# JTAG_Trace.net
KiCad netlist of a schematic drawn in Altium Designer
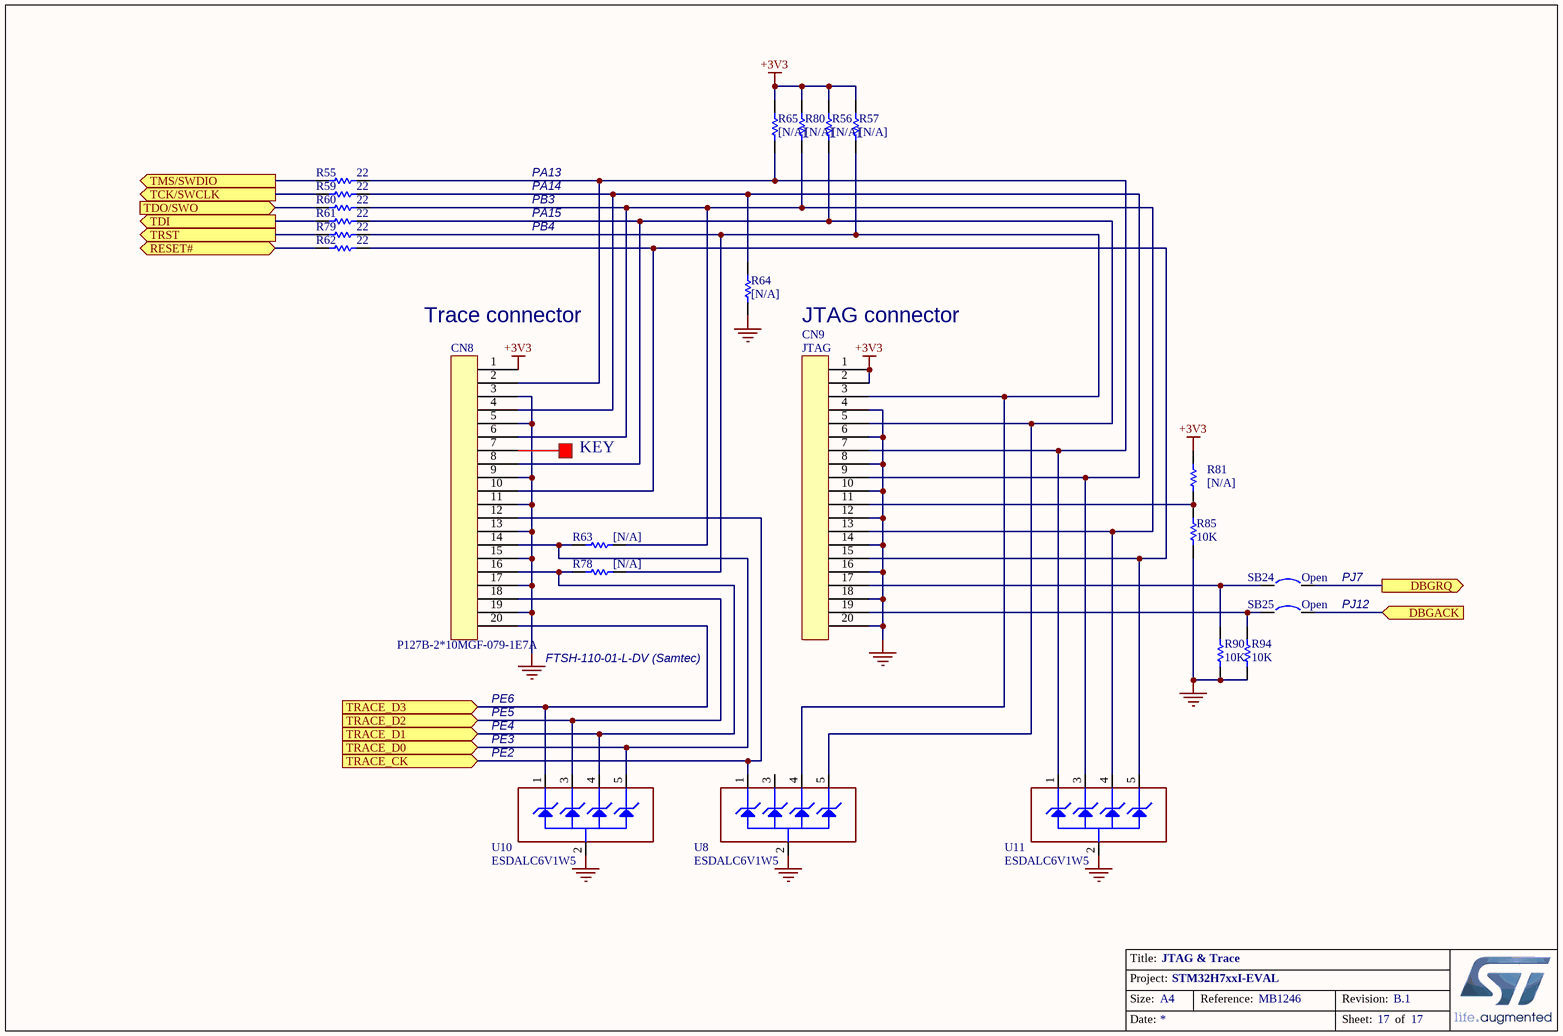
[diagram p0: JTAG&Trace.SchDoc]

(export (version "E")
  (design (tool "Eeschema 10.0.6"))
  (components
    (comp (ref "CN8")
      (value "P127B-2*10MGF-079-1E7A")
      (footprint "FTSH-110-01-L-DV")
      (libsource (lib "*") (part "20PIN1"))
    )
    (comp (ref "CN9") (value "JTAG") (footprint "IDC20S") (libsource (lib "*") (part "20PIN1")))
    (comp (ref "R55")
      (value "22")
      (footprint "0603R")
      (description "Resistor")
      (fields (field (name "PUBLISHER") "Altium Limited"))
      (libsource (lib "Miscellaneous Devices") (part "Res1"))
    )
    (comp (ref "R56")
      (value "[N/A]")
      (footprint "0603R")
      (description "Resistor")
      (fields (field (name "PUBLISHER") "Altium Limited"))
      (libsource (lib "Miscellaneous Devices") (part "Res1"))
    )
    (comp (ref "R57")
      (value "[N/A]")
      (footprint "0603R")
      (description "Resistor")
      (fields (field (name "PUBLISHER") "Altium Limited"))
      (libsource (lib "Miscellaneous Devices") (part "Res1"))
    )
    (comp (ref "R59")
      (value "22")
      (footprint "0603R")
      (description "Resistor")
      (fields (field (name "PUBLISHER") "Altium Limited"))
      (libsource (lib "Miscellaneous Devices") (part "Res1"))
    )
    (comp (ref "R60")
      (value "22")
      (footprint "0603R")
      (description "Resistor")
      (fields (field (name "PUBLISHER") "Altium Limited"))
      (libsource (lib "Miscellaneous Devices") (part "Res1"))
    )
    (comp (ref "R61")
      (value "22")
      (footprint "0603R")
      (description "Resistor")
      (fields (field (name "PUBLISHER") "Altium Limited"))
      (libsource (lib "Miscellaneous Devices") (part "Res1"))
    )
    (comp (ref "R62")
      (value "22")
      (footprint "0603R")
      (description "Resistor")
      (fields (field (name "PUBLISHER") "Altium Limited"))
      (libsource (lib "Miscellaneous Devices") (part "Res1"))
    )
    (comp (ref "R63")
      (value "[N/A]")
      (footprint "0603R")
      (description "Resistor")
      (fields (field (name "PUBLISHER") "Altium Limited"))
      (libsource (lib "Miscellaneous Devices") (part "Res1"))
    )
    (comp (ref "R64")
      (value "[N/A]")
      (footprint "0603R")
      (description "Resistor")
      (fields (field (name "PUBLISHER") "Altium Limited"))
      (libsource (lib "Miscellaneous Devices") (part "Res1"))
    )
    (comp (ref "R65")
      (value "[N/A]")
      (footprint "0603R")
      (description "Resistor")
      (fields (field (name "PUBLISHER") "Altium Limited"))
      (libsource (lib "Miscellaneous Devices") (part "Res1"))
    )
    (comp (ref "R78")
      (value "[N/A]")
      (footprint "0603R")
      (description "Resistor")
      (fields (field (name "PUBLISHER") "Altium Limited"))
      (libsource (lib "Miscellaneous Devices") (part "Res1"))
    )
    (comp (ref "R79")
      (value "22")
      (footprint "0603R")
      (description "Resistor")
      (fields (field (name "PUBLISHER") "Altium Limited"))
      (libsource (lib "Miscellaneous Devices") (part "Res1"))
    )
    (comp (ref "R80")
      (value "[N/A]")
      (footprint "0603R")
      (description "Resistor")
      (fields (field (name "PUBLISHER") "Altium Limited"))
      (libsource (lib "Miscellaneous Devices") (part "Res1"))
    )
    (comp (ref "R81")
      (value "[N/A]")
      (footprint "0603R")
      (description "Resistor")
      (fields (field (name "PUBLISHER") "Altium Limited"))
      (libsource (lib "Miscellaneous Devices") (part "Res1"))
    )
    (comp (ref "R85")
      (value "10K")
      (footprint "0603R")
      (description "Resistor")
      (fields (field (name "PUBLISHER") "Altium Limited"))
      (libsource (lib "Miscellaneous Devices") (part "Res1"))
    )
    (comp (ref "R90")
      (value "10K")
      (footprint "0603R")
      (description "Resistor")
      (fields (field (name "PUBLISHER") "Altium Limited"))
      (libsource (lib "Miscellaneous Devices") (part "Res1"))
    )
    (comp (ref "R94")
      (value "10K")
      (footprint "0603R")
      (description "Resistor")
      (fields (field (name "PUBLISHER") "Altium Limited"))
      (libsource (lib "Miscellaneous Devices") (part "Res1"))
    )
    (comp (ref "SB24")
      (value "Open")
      (footprint "SB_0603")
      (description "Circuit Breaker")
      (fields (field (name "PUBLISHER") "Altium Limited"))
      (libsource (lib "MB1165") (part "Circuit Breaker"))
    )
    (comp (ref "SB25")
      (value "Open")
      (footprint "SB_0603")
      (description "Circuit Breaker")
      (fields (field (name "PUBLISHER") "Altium Limited"))
      (libsource (lib "MB1165") (part "Circuit Breaker"))
    )
    (comp (ref "U8")
      (value "ESDALC6V1W5")
      (footprint "SOT-353")
      (description "Dual Transil array for ESD protection")
      (libsource (lib "MB1167_1") (part "ESDALC6V1W5"))
    )
    (comp (ref "U10")
      (value "ESDALC6V1W5")
      (footprint "SOT-353")
      (description "Dual Transil array for ESD protection")
      (libsource (lib "MB1167_1") (part "ESDALC6V1W5"))
    )
    (comp (ref "U11")
      (value "ESDALC6V1W5")
      (footprint "SOT-353")
      (description "Dual Transil array for ESD protection")
      (libsource (lib "MB1167_1") (part "ESDALC6V1W5"))
    )
  )
  (nets
    (net (code "1") (name "+3V3") (class "Default")
      (node (ref "CN8") (pin "1") (pintype "passive"))
      (node (ref "CN9") (pin "1") (pintype "passive"))
      (node (ref "CN9") (pin "2") (pintype "passive"))
      (node (ref "R56") (pin "2") (pinfunction "2_2") (pintype "passive"))
      (node (ref "R57") (pin "2") (pinfunction "2_2") (pintype "passive"))
      (node (ref "R65") (pin "2") (pinfunction "2_2") (pintype "passive"))
      (node (ref "R80") (pin "2") (pinfunction "2_2") (pintype "passive"))
      (node (ref "R81") (pin "2") (pinfunction "2_2") (pintype "passive"))
    )
    (net (code "2") (name "/DBGACK") (class "Default")
      (node (ref "SB25") (pin "2") (pinfunction "2_2") (pintype "passive"))
    )
    (net (code "3") (name "/DBGRQ") (class "Default")
      (node (ref "SB24") (pin "2") (pinfunction "2_2") (pintype "passive"))
    )
    (net (code "4") (name "/RESET#") (class "Default")
      (node (ref "R62") (pin "2") (pinfunction "2_2") (pintype "passive"))
    )
    (net (code "5") (name "/TCK{slash}SWCLK") (class "Default")
      (node (ref "R59") (pin "2") (pinfunction "2_2") (pintype "passive"))
    )
    (net (code "6") (name "/TDI") (class "Default")
      (node (ref "R61") (pin "2") (pinfunction "2_2") (pintype "passive"))
    )
    (net (code "7") (name "/TDO{slash}SWO") (class "Default")
      (node (ref "R60") (pin "2") (pinfunction "2_2") (pintype "passive"))
    )
    (net (code "8") (name "/TMS{slash}SWDIO") (class "Default")
      (node (ref "R55") (pin "2") (pinfunction "2_2") (pintype "passive"))
    )
    (net (code "9") (name "/TRACE_CK") (class "Default")
      (node (ref "CN8") (pin "12") (pintype "passive"))
      (node (ref "U8") (pin "1") (pinfunction "IO1_1") (pintype "passive"))
    )
    (net (code "10") (name "/TRACE_D0") (class "Default")
      (node (ref "CN8") (pin "14") (pintype "passive"))
      (node (ref "R63") (pin "1") (pinfunction "1_1") (pintype "passive"))
      (node (ref "U10") (pin "5") (pinfunction "IO4_5") (pintype "passive"))
    )
    (net (code "11") (name "/TRACE_D1") (class "Default")
      (node (ref "CN8") (pin "16") (pintype "passive"))
      (node (ref "R78") (pin "1") (pinfunction "1_1") (pintype "passive"))
      (node (ref "U10") (pin "4") (pinfunction "IO3_4") (pintype "passive"))
    )
    (net (code "12") (name "/TRACE_D2") (class "Default")
      (node (ref "CN8") (pin "18") (pintype "passive"))
      (node (ref "U10") (pin "3") (pinfunction "IO2_3") (pintype "passive"))
    )
    (net (code "13") (name "/TRACE_D3") (class "Default")
      (node (ref "CN8") (pin "20") (pintype "passive"))
      (node (ref "U10") (pin "1") (pinfunction "IO1_1") (pintype "passive"))
    )
    (net (code "14") (name "/TRST") (class "Default")
      (node (ref "R79") (pin "2") (pinfunction "2_2") (pintype "passive"))
    )
    (net (code "15") (name "GND") (class "Default")
      (node (ref "CN8") (pin "11") (pintype "passive"))
      (node (ref "CN8") (pin "13") (pintype "passive"))
      (node (ref "CN8") (pin "15") (pintype "passive"))
      (node (ref "CN8") (pin "17") (pintype "passive"))
      (node (ref "CN8") (pin "19") (pintype "passive"))
      (node (ref "CN8") (pin "3") (pintype "passive"))
      (node (ref "CN8") (pin "5") (pintype "passive"))
      (node (ref "CN8") (pin "9") (pintype "passive"))
      (node (ref "CN9") (pin "10") (pintype "passive"))
      (node (ref "CN9") (pin "12") (pintype "passive"))
      (node (ref "CN9") (pin "14") (pintype "passive"))
      (node (ref "CN9") (pin "16") (pintype "passive"))
      (node (ref "CN9") (pin "18") (pintype "passive"))
      (node (ref "CN9") (pin "20") (pintype "passive"))
      (node (ref "CN9") (pin "4") (pintype "passive"))
      (node (ref "CN9") (pin "6") (pintype "passive"))
      (node (ref "CN9") (pin "8") (pintype "passive"))
      (node (ref "R64") (pin "1") (pinfunction "1_1") (pintype "passive"))
      (node (ref "R85") (pin "1") (pinfunction "1_1") (pintype "passive"))
      (node (ref "R90") (pin "1") (pinfunction "1_1") (pintype "passive"))
      (node (ref "R94") (pin "1") (pinfunction "1_1") (pintype "passive"))
      (node (ref "U10") (pin "2") (pinfunction "GND_2") (pintype "passive"))
      (node (ref "U11") (pin "2") (pinfunction "GND_2") (pintype "passive"))
      (node (ref "U8") (pin "2") (pinfunction "GND_2") (pintype "passive"))
    )
    (net (code "16") (name "Net-(CN9-Pad11)") (class "Default")
      (node (ref "CN9") (pin "11") (pintype "passive"))
      (node (ref "R81") (pin "1") (pinfunction "1_1") (pintype "passive"))
      (node (ref "R85") (pin "2") (pinfunction "2_2") (pintype "passive"))
    )
    (net (code "17") (name "Net-(CN9-Pad17)") (class "Default")
      (node (ref "CN9") (pin "17") (pintype "passive"))
      (node (ref "R90") (pin "2") (pinfunction "2_2") (pintype "passive"))
      (node (ref "SB24") (pin "1") (pinfunction "1_1") (pintype "passive"))
    )
    (net (code "18") (name "Net-(CN9-Pad19)") (class "Default")
      (node (ref "CN9") (pin "19") (pintype "passive"))
      (node (ref "R94") (pin "2") (pinfunction "2_2") (pintype "passive"))
      (node (ref "SB25") (pin "1") (pinfunction "1_1") (pintype "passive"))
    )
    (net (code "19") (name "Net-(U8-IO3)") (class "Default")
      (node (ref "CN9") (pin "3") (pintype "passive"))
      (node (ref "R57") (pin "1") (pinfunction "1_1") (pintype "passive"))
      (node (ref "R78") (pin "2") (pinfunction "2_2") (pintype "passive"))
      (node (ref "R79") (pin "1") (pinfunction "1_1") (pintype "passive"))
      (node (ref "U8") (pin "4") (pinfunction "IO3_4") (pintype "passive"))
    )
    (net (code "20") (name "Net-(U8-IO4)") (class "Default")
      (node (ref "CN8") (pin "8") (pintype "passive"))
      (node (ref "CN9") (pin "5") (pintype "passive"))
      (node (ref "R56") (pin "1") (pinfunction "1_1") (pintype "passive"))
      (node (ref "R61") (pin "1") (pinfunction "1_1") (pintype "passive"))
      (node (ref "U8") (pin "5") (pinfunction "IO4_5") (pintype "passive"))
    )
    (net (code "21") (name "Net-(U11-IO1)") (class "Default")
      (node (ref "CN8") (pin "2") (pintype "passive"))
      (node (ref "CN9") (pin "7") (pintype "passive"))
      (node (ref "R55") (pin "1") (pinfunction "1_1") (pintype "passive"))
      (node (ref "R65") (pin "1") (pinfunction "1_1") (pintype "passive"))
      (node (ref "U11") (pin "1") (pinfunction "IO1_1") (pintype "passive"))
    )
    (net (code "22") (name "Net-(U11-IO2)") (class "Default")
      (node (ref "CN8") (pin "4") (pintype "passive"))
      (node (ref "CN9") (pin "9") (pintype "passive"))
      (node (ref "R59") (pin "1") (pinfunction "1_1") (pintype "passive"))
      (node (ref "R64") (pin "2") (pinfunction "2_2") (pintype "passive"))
      (node (ref "U11") (pin "3") (pinfunction "IO2_3") (pintype "passive"))
    )
    (net (code "23") (name "Net-(U11-IO3)") (class "Default")
      (node (ref "CN8") (pin "6") (pintype "passive"))
      (node (ref "CN9") (pin "13") (pintype "passive"))
      (node (ref "R60") (pin "1") (pinfunction "1_1") (pintype "passive"))
      (node (ref "R63") (pin "2") (pinfunction "2_2") (pintype "passive"))
      (node (ref "R80") (pin "1") (pinfunction "1_1") (pintype "passive"))
      (node (ref "U11") (pin "4") (pinfunction "IO3_4") (pintype "passive"))
    )
    (net (code "24") (name "Net-(U11-IO4)") (class "Default")
      (node (ref "CN8") (pin "10") (pintype "passive"))
      (node (ref "CN9") (pin "15") (pintype "passive"))
      (node (ref "R62") (pin "1") (pinfunction "1_1") (pintype "passive"))
      (node (ref "U11") (pin "5") (pinfunction "IO4_5") (pintype "passive"))
    )
    (net (code "25") (name "unconnected-(CN8-Pad7)") (class "Default")
      (node (ref "CN8") (pin "7") (pintype "passive"))
    )
    (net (code "26") (name "unconnected-(U8-IO2-Pad3)") (class "Default")
      (node (ref "U8") (pin "3") (pinfunction "IO2_3") (pintype "passive"))
    )
  )
)
